# NixiePower.net
KiCad netlist of a schematic drawn in EAGLE
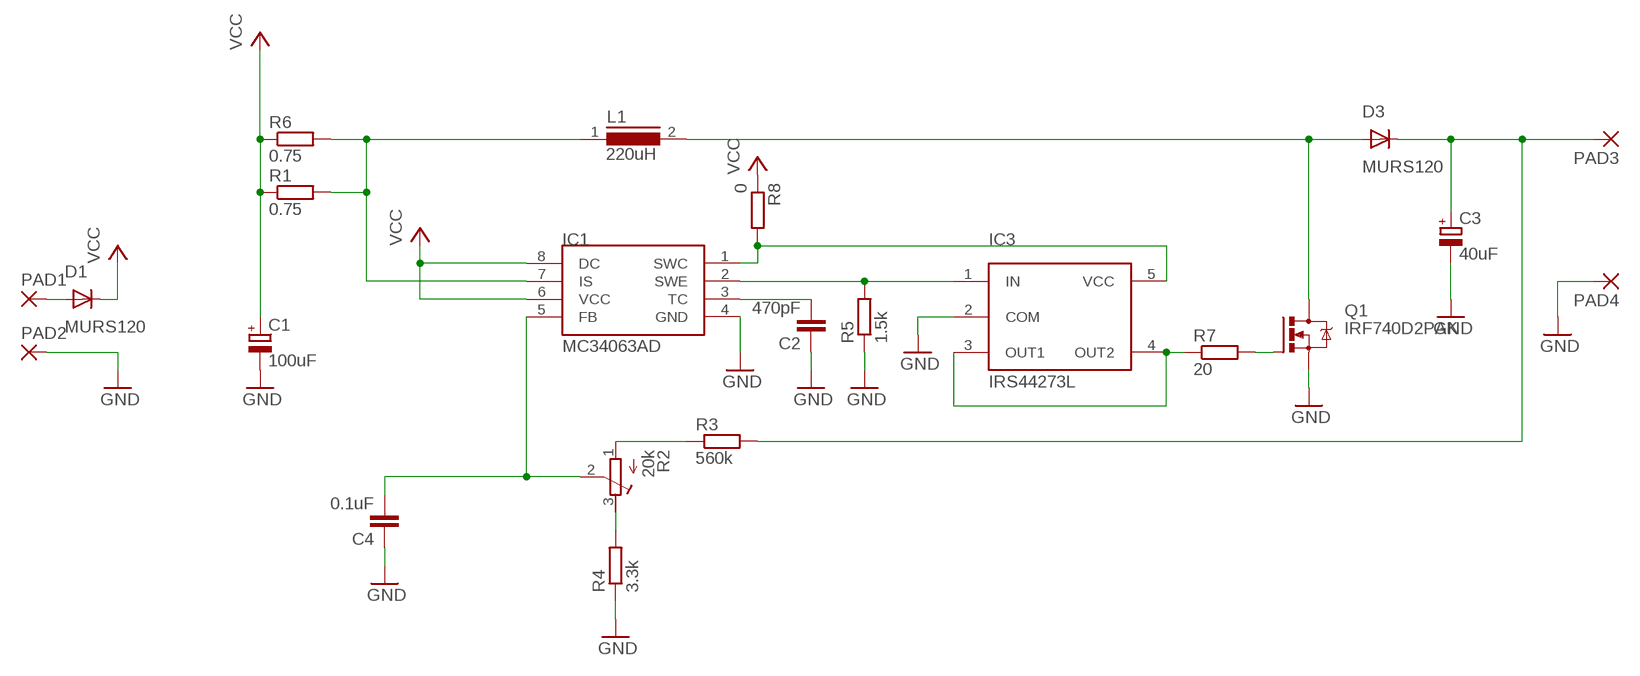
[diagram p0: schematic, sheet 1]

(export (version "E")
  (design (tool "Eeschema 10.0.6"))
  (components
    (comp (ref "C1")
      (value "100uF")
      (footprint "eagle-import:D_7343-31R")
      (libsource (lib "eagle-import") (part "CPOL-EUD/7343-31R"))
    )
    (comp (ref "C2")
      (value "470pF")
      (footprint "eagle-import:C1206K")
      (libsource (lib "eagle-import") (part "C-EUC1206K"))
    )
    (comp (ref "C3")
      (value "40uF")
      (footprint "eagle-import:C_6032-28R")
      (libsource (lib "eagle-import") (part "CPOL-EUC/6032-28R"))
    )
    (comp (ref "C4")
      (value "0.1uF")
      (footprint "eagle-import:C1206K")
      (libsource (lib "eagle-import") (part "C-EUC1206K"))
    )
    (comp (ref "D1")
      (value "MURS120")
      (footprint "eagle-import:DO214AA")
      (libsource (lib "eagle-import") (part "DIODE-DO214AA"))
    )
    (comp (ref "D3")
      (value "MURS120")
      (footprint "eagle-import:DO214AA")
      (libsource (lib "eagle-import") (part "DIODE-DO214AA"))
    )
    (comp (ref "IC1")
      (value "MC34063AD")
      (footprint "eagle-import:SOIC8")
      (libsource (lib "eagle-import") (part "MC34063AD"))
    )
    (comp (ref "IC3")
      (value "IRS44273L")
      (footprint "eagle-import:SOT23-5")
      (libsource (lib "eagle-import") (part "IRS44273L"))
    )
    (comp (ref "L1")
      (value "220uH")
      (footprint "eagle-import:DR125")
      (libsource (lib "eagle-import") (part "DR125"))
    )
    (comp (ref "PAD1")
      (value "SMD5")
      (footprint "eagle-import:SMD2,54-5,08")
      (libsource (lib "eagle-import") (part "SMD5"))
    )
    (comp (ref "PAD2")
      (value "SMD5")
      (footprint "eagle-import:SMD2,54-5,08")
      (libsource (lib "eagle-import") (part "SMD5"))
    )
    (comp (ref "PAD3")
      (value "SMD5")
      (footprint "eagle-import:SMD2,54-5,08")
      (libsource (lib "eagle-import") (part "SMD5"))
    )
    (comp (ref "PAD4")
      (value "SMD5")
      (footprint "eagle-import:SMD2,54-5,08")
      (libsource (lib "eagle-import") (part "SMD5"))
    )
    (comp (ref "Q1")
      (value "IRF740D2PAK")
      (footprint "eagle-import:D2PAK")
      (libsource (lib "eagle-import") (part "IRF740D2PAK"))
    )
    (comp (ref "R1")
      (value "0.75")
      (footprint "eagle-import:R1206")
      (libsource (lib "eagle-import") (part "R-EU_R1206"))
    )
    (comp (ref "R2")
      (value "20k")
      (footprint "eagle-import:RTRIM4G_J")
      (libsource (lib "eagle-import") (part "R-TRIMM4G/J"))
    )
    (comp (ref "R3")
      (value "560k")
      (footprint "eagle-import:R1206")
      (libsource (lib "eagle-import") (part "R-EU_R1206"))
    )
    (comp (ref "R4")
      (value "3.3k")
      (footprint "eagle-import:R1206")
      (libsource (lib "eagle-import") (part "R-EU_R1206"))
    )
    (comp (ref "R5")
      (value "1.5k")
      (footprint "eagle-import:R1206")
      (libsource (lib "eagle-import") (part "R-EU_R1206"))
    )
    (comp (ref "R6")
      (value "0.75")
      (footprint "eagle-import:R1206")
      (libsource (lib "eagle-import") (part "R-EU_R1206"))
    )
    (comp (ref "R7")
      (value "20")
      (footprint "eagle-import:R1206")
      (libsource (lib "eagle-import") (part "R-EU_R1206"))
    )
    (comp (ref "R8")
      (value "0")
      (footprint "eagle-import:R1206")
      (libsource (lib "eagle-import") (part "R-EU_R1206"))
    )
  )
  (nets
    (net (code "1") (name "GND") (class "Default")
      (node (ref "C1") (pin "-") (pinfunction "-_-") (pintype "passive"))
      (node (ref "C2") (pin "1") (pinfunction "1_1") (pintype "passive"))
      (node (ref "C3") (pin "-") (pinfunction "-_-") (pintype "passive"))
      (node (ref "C4") (pin "1") (pinfunction "1_1") (pintype "passive"))
      (node (ref "IC1") (pin "4") (pinfunction "GND_4") (pintype "passive"))
      (node (ref "IC3") (pin "2") (pinfunction "COM_2") (pintype "power_in"))
      (node (ref "PAD2") (pin "1") (pinfunction "P_1") (pintype "passive"))
      (node (ref "PAD4") (pin "1") (pinfunction "P_1") (pintype "passive"))
      (node (ref "Q1") (pin "3") (pinfunction "S_3") (pintype "passive"))
      (node (ref "R4") (pin "1") (pinfunction "1_1") (pintype "passive"))
      (node (ref "R5") (pin "1") (pinfunction "1_1") (pintype "passive"))
    )
    (net (code "2") (name "Net-(IC1-FB)") (class "Default")
      (node (ref "C4") (pin "2") (pinfunction "2_2") (pintype "passive"))
      (node (ref "IC1") (pin "5") (pinfunction "FB_5") (pintype "passive"))
      (node (ref "R2") (pin "2") (pinfunction "S_2") (pintype "passive"))
    )
    (net (code "3") (name "Net-(IC1-IS)") (class "Default")
      (node (ref "IC1") (pin "7") (pinfunction "IS_7") (pintype "passive"))
      (node (ref "L1") (pin "1") (pinfunction "1_1") (pintype "passive"))
      (node (ref "R1") (pin "2") (pinfunction "2_2") (pintype "passive"))
      (node (ref "R6") (pin "2") (pinfunction "2_2") (pintype "passive"))
    )
    (net (code "4") (name "Net-(IC1-SWC)") (class "Default")
      (node (ref "IC1") (pin "1") (pinfunction "SWC_1") (pintype "passive"))
      (node (ref "IC3") (pin "5") (pinfunction "VCC_5") (pintype "power_in"))
      (node (ref "R8") (pin "2") (pinfunction "2_2") (pintype "passive"))
    )
    (net (code "5") (name "Net-(IC1-SWE)") (class "Default")
      (node (ref "IC1") (pin "2") (pinfunction "SWE_2") (pintype "passive"))
      (node (ref "IC3") (pin "1") (pinfunction "IN_1") (pintype "input"))
      (node (ref "R5") (pin "2") (pinfunction "2_2") (pintype "passive"))
    )
    (net (code "6") (name "Net-(IC1-TC)") (class "Default")
      (node (ref "C2") (pin "2") (pinfunction "2_2") (pintype "passive"))
      (node (ref "IC1") (pin "3") (pinfunction "TC_3") (pintype "passive"))
    )
    (net (code "7") (name "Net-(IC3-OUT1)") (class "Default")
      (node (ref "IC3") (pin "3") (pinfunction "OUT1_3") (pintype "output"))
      (node (ref "IC3") (pin "4") (pinfunction "OUT2_4") (pintype "output"))
      (node (ref "R7") (pin "1") (pinfunction "1_1") (pintype "passive"))
    )
    (net (code "8") (name "Net-(PAD1-P)") (class "Default")
      (node (ref "D1") (pin "A") (pinfunction "A_A") (pintype "passive"))
      (node (ref "PAD1") (pin "1") (pinfunction "P_1") (pintype "passive"))
    )
    (net (code "9") (name "Net-(PAD3-P)") (class "Default")
      (node (ref "C3") (pin "+") (pinfunction "+_+") (pintype "passive"))
      (node (ref "D3") (pin "C") (pinfunction "C_C") (pintype "passive"))
      (node (ref "PAD3") (pin "1") (pinfunction "P_1") (pintype "passive"))
      (node (ref "R3") (pin "2") (pinfunction "2_2") (pintype "passive"))
    )
    (net (code "10") (name "Net-(Q1-D)") (class "Default")
      (node (ref "D3") (pin "A") (pinfunction "A_A") (pintype "passive"))
      (node (ref "L1") (pin "2") (pinfunction "2_2") (pintype "passive"))
      (node (ref "Q1") (pin "4") (pinfunction "D_4") (pintype "passive"))
    )
    (net (code "11") (name "Net-(Q1-G)") (class "Default")
      (node (ref "Q1") (pin "1") (pinfunction "G_1") (pintype "passive"))
      (node (ref "R7") (pin "2") (pinfunction "2_2") (pintype "passive"))
    )
    (net (code "12") (name "Net-(R2-A)") (class "Default")
      (node (ref "R2") (pin "1") (pinfunction "A_1") (pintype "passive"))
      (node (ref "R3") (pin "1") (pinfunction "1_1") (pintype "passive"))
    )
    (net (code "13") (name "Net-(R2-E)") (class "Default")
      (node (ref "R2") (pin "3") (pinfunction "E_3") (pintype "passive"))
      (node (ref "R4") (pin "2") (pinfunction "2_2") (pintype "passive"))
    )
    (net (code "14") (name "VCC") (class "Default")
      (node (ref "C1") (pin "+") (pinfunction "+_+") (pintype "passive"))
      (node (ref "D1") (pin "C") (pinfunction "C_C") (pintype "passive"))
      (node (ref "IC1") (pin "6") (pinfunction "VCC_6") (pintype "passive"))
      (node (ref "IC1") (pin "8") (pinfunction "DC_8") (pintype "passive"))
      (node (ref "R1") (pin "1") (pinfunction "1_1") (pintype "passive"))
      (node (ref "R6") (pin "1") (pinfunction "1_1") (pintype "passive"))
      (node (ref "R8") (pin "1") (pinfunction "1_1") (pintype "passive"))
    )
  )
)
